# LED_Board.net
KiCad netlist of a schematic drawn in EAGLE
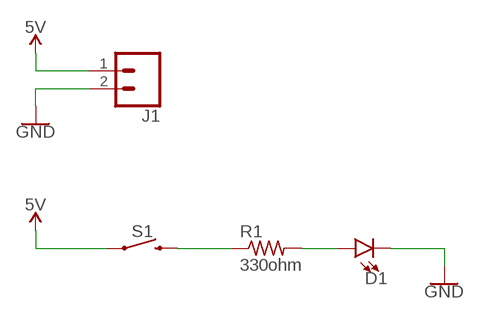
[diagram p0: schematic, sheet 1]

(export (version "E")
  (design (tool "Eeschema 10.0.6"))
  (components
    (comp (ref "D1")
      (value "LED3MM")
      (footprint "eagle-import:LED_3MM")
      (libsource (lib "eagle-import") (part "LED3MM"))
    )
    (comp (ref "J1")
      (value "CONN_025MM")
      (footprint "eagle-import:SCREWTERMINAL-5MM-2")
      (libsource (lib "eagle-import") (part "CONN_025MM"))
    )
    (comp (ref "R1")
      (value "330ohm")
      (footprint "eagle-import:R0805")
      (libsource (lib "eagle-import") (part "R-US_R0805"))
    )
    (comp (ref "S1")
      (value "MOMENTARY-SWITCH-SPST-SMD-4.5MM")
      (footprint "eagle-import:TACTILE_SWITCH_SMD_4.5MM")
      (libsource (lib "eagle-import") (part "MOMENTARY-SWITCH-SPST-SMD-4.5MM"))
    )
  )
  (nets
    (net (code "1") (name "5V") (class "Default")
      (node (ref "J1") (pin "1") (pinfunction "1_1") (pintype "passive"))
      (node (ref "S1") (pin "2") (pinfunction "1_2") (pintype "passive"))
      (node (ref "S1") (pin "3") (pinfunction "1_3") (pintype "passive"))
    )
    (net (code "2") (name "GND") (class "Default")
      (node (ref "D1") (pin "K") (pinfunction "C_K") (pintype "passive"))
      (node (ref "J1") (pin "2") (pinfunction "2_2") (pintype "passive"))
    )
    (net (code "3") (name "Net-(D1-PadA)") (class "Default")
      (node (ref "D1") (pin "A") (pinfunction "A_A") (pintype "passive"))
      (node (ref "R1") (pin "2") (pinfunction "2_2") (pintype "passive"))
    )
    (net (code "4") (name "Net-(R1-Pad1)") (class "Default")
      (node (ref "R1") (pin "1") (pinfunction "1_1") (pintype "passive"))
      (node (ref "S1") (pin "1") (pinfunction "2_1") (pintype "passive"))
      (node (ref "S1") (pin "4") (pinfunction "2_4") (pintype "passive"))
    )
  )
)
